# ST_LINK_V2.net
KiCad netlist of a schematic drawn in Altium Designer
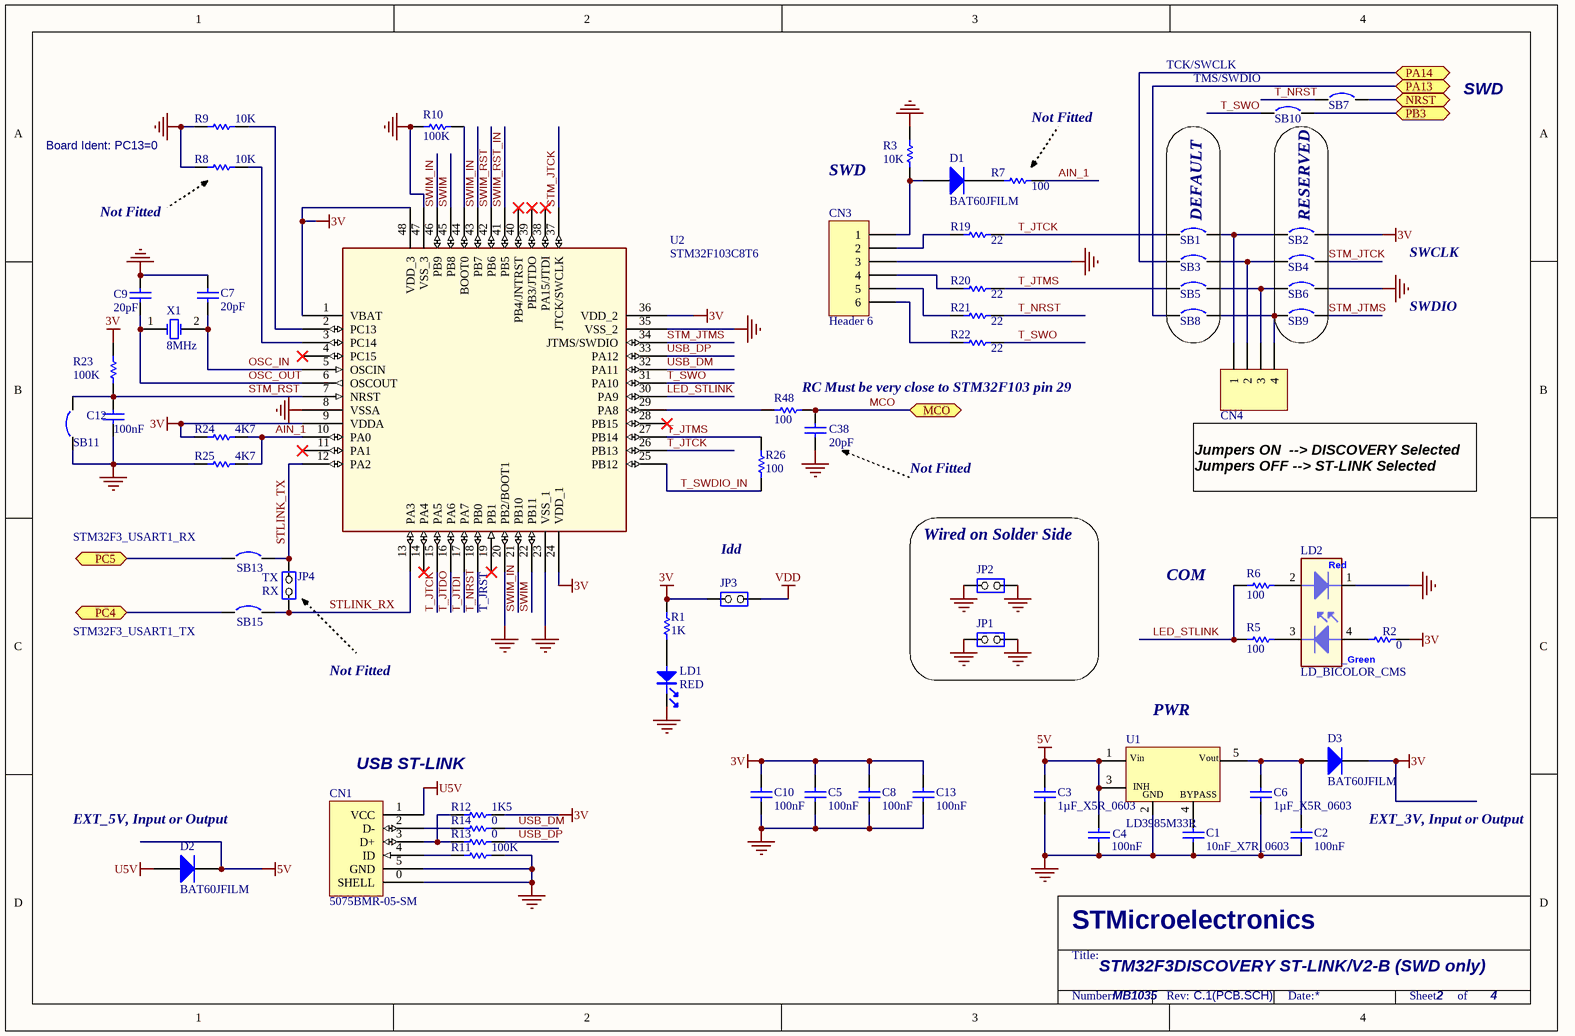
[diagram p0: ST_LINK_V2.SCHDOC]

(export (version "E")
  (design (tool "Eeschema 10.0.6"))
  (components
    (comp (ref "C1")
      (value "10nF_X7R_0603")
      (footprint "0603C")
      (description "0603  X7R 10NF")
      (fields (field (name "TOLERANCE") "10%"))
      (libsource (lib "MB963_1") (part "CAP SMD 0603  X7R 10000PF 50V 10%"))
    )
    (comp (ref "C2")
      (value "100nF")
      (footprint "0603C")
      (description "Capacitor")
      (fields (field (name "PUBLISHER") "Altium Limited"))
      (libsource (lib "MB915_1") (part "Cap"))
    )
    (comp (ref "C3")
      (value "1µF_X5R_0603")
      (footprint "0603C")
      (description "0603  X5R 1µF")
      (fields (field (name "TOLERANCE") "10%"))
      (libsource (lib "MB963_1") (part "CAP SMD 0603  X5R 1µF 25V 10%"))
    )
    (comp (ref "C4")
      (value "100nF")
      (footprint "0603C")
      (description "Capacitor")
      (fields (field (name "PUBLISHER") "Altium Limited"))
      (libsource (lib "MB915_1") (part "Cap"))
    )
    (comp (ref "C5")
      (value "100nF")
      (footprint "0402C")
      (description "Capacitor")
      (fields (field (name "PUBLISHER") "Altium Limited"))
      (libsource (lib "MB915_1") (part "Cap"))
    )
    (comp (ref "C6")
      (value "1µF_X5R_0603")
      (footprint "0603C")
      (description "0603  X5R 1µF")
      (fields (field (name "TOLERANCE") "10%"))
      (libsource (lib "MB963_1") (part "CAP SMD 0603  X5R 1µF 25V 10%"))
    )
    (comp (ref "C7")
      (value "20pF")
      (footprint "0402C")
      (description "Capacitor")
      (fields (field (name "PUBLISHER") "Altium Limited"))
      (libsource (lib "MB915_1") (part "Cap"))
    )
    (comp (ref "C8")
      (value "100nF")
      (footprint "0402C")
      (description "Capacitor")
      (fields (field (name "PUBLISHER") "Altium Limited"))
      (libsource (lib "MB915_1") (part "Cap"))
    )
    (comp (ref "C9")
      (value "20pF")
      (footprint "0402C")
      (description "Capacitor")
      (fields (field (name "PUBLISHER") "Altium Limited"))
      (libsource (lib "MB915_1") (part "Cap"))
    )
    (comp (ref "C10")
      (value "100nF")
      (footprint "0402C")
      (description "Capacitor")
      (fields (field (name "PUBLISHER") "Altium Limited"))
      (libsource (lib "MB915_1") (part "Cap"))
    )
    (comp (ref "C12")
      (value "100nF")
      (footprint "0402C")
      (description "Capacitor")
      (fields (field (name "PUBLISHER") "Altium Limited"))
      (libsource (lib "MB915_1") (part "Cap"))
    )
    (comp (ref "C13")
      (value "100nF")
      (footprint "0402C")
      (description "Capacitor")
      (fields (field (name "PUBLISHER") "Altium Limited"))
      (libsource (lib "MB915_1") (part "Cap"))
    )
    (comp (ref "C38")
      (value "20pF")
      (footprint "0402C")
      (description "Capacitor")
      (fields (field (name "PUBLISHER") "Altium Limited"))
      (libsource (lib "MB915_1") (part "Cap"))
    )
    (comp (ref "CN1")
      (value "5075BMR-05-SM")
      (footprint "USB-MINI-B-SMD")
      (libsource (lib "MCD_TOOLS") (part "USB-MINI-typeB connector"))
    )
    (comp (ref "CN3")
      (value "Header 6")
      (footprint "HDR1X6")
      (description "Header, 6-Pin")
      (fields (field (name "PUBLISHER") "Altium Limited"))
      (libsource (lib "Miscellaneous Connectors") (part "Header 6"))
    )
    (comp (ref "CN4")
      (value "Header 4")
      (footprint "Header 4")
      (description "Header, 4-Pin")
      (fields (field (name "PUBLISHER") "Altium Limited"))
      (libsource (lib "MB963_1") (part "Header 4"))
    )
    (comp (ref "D1")
      (value "BAT60JFILM")
      (footprint "SOD323/A")
      (fields (field (name "PUBLISHER") "Altium Limited"))
      (libsource (lib "MB997") (part "BAT60JFILM"))
    )
    (comp (ref "D2")
      (value "BAT60JFILM")
      (footprint "SOD323/A")
      (fields (field (name "PUBLISHER") "Altium Limited"))
      (libsource (lib "MB997") (part "BAT60JFILM"))
    )
    (comp (ref "D3")
      (value "BAT60JFILM")
      (footprint "SOD323/A")
      (fields (field (name "PUBLISHER") "Altium Limited"))
      (libsource (lib "MB997") (part "BAT60JFILM"))
    )
    (comp (ref "JP1") (value "~") (footprint "SIP2/2.54") (libsource (lib "*") (part "JP2")))
    (comp (ref "JP2") (value "~") (footprint "SIP2/2.54") (libsource (lib "*") (part "JP2")))
    (comp (ref "JP3") (value "~") (footprint "SIP2/2.54") (libsource (lib "*") (part "JP2")))
    (comp (ref "JP4") (value "JP2") (footprint "SIP2/2.54") (libsource (lib "MCD_TOOLS") (part "JP2")))
    (comp (ref "LD1") (value "RED") (footprint "0603D") (libsource (lib "MB963_1") (part "PHOTO")))
    (comp (ref "LD2")
      (value "LD_BICOLOR_CMS")
      (footprint "HSMF-A201")
      (description "Bicolor Led")
      (libsource (lib "MB963") (part "LD_BICOLOR_CMS"))
    )
    (comp (ref "R1")
      (value "1K")
      (footprint "0402R")
      (description "Resistor")
      (fields (field (name "PUBLISHER") "Altium Limited"))
      (libsource (lib "MB915_1") (part "res1"))
    )
    (comp (ref "R2")
      (value "0")
      (footprint "0402R")
      (description "Resistor")
      (fields (field (name "PUBLISHER") "Altium Limited"))
      (libsource (lib "MB915_1") (part "res1"))
    )
    (comp (ref "R3")
      (value "10K")
      (footprint "0402R")
      (description "Resistor")
      (fields (field (name "PUBLISHER") "Altium Limited"))
      (libsource (lib "MB915_1") (part "res1"))
    )
    (comp (ref "R5")
      (value "100")
      (footprint "0402R")
      (description "Resistor")
      (fields (field (name "PUBLISHER") "Altium Limited"))
      (libsource (lib "MB915_1") (part "res1"))
    )
    (comp (ref "R6")
      (value "100")
      (footprint "0402R")
      (description "Resistor")
      (fields (field (name "PUBLISHER") "Altium Limited"))
      (libsource (lib "MB915_1") (part "res1"))
    )
    (comp (ref "R7")
      (value "100")
      (footprint "0402R")
      (description "Resistor")
      (fields (field (name "PUBLISHER") "Altium Limited"))
      (libsource (lib "MB915_1") (part "res1"))
    )
    (comp (ref "R8")
      (value "10K")
      (footprint "0402R")
      (description "Resistor")
      (fields (field (name "PUBLISHER") "Altium Limited"))
      (libsource (lib "MB915_1") (part "res1"))
    )
    (comp (ref "R9")
      (value "10K")
      (footprint "0402R")
      (description "Resistor")
      (fields (field (name "PUBLISHER") "Altium Limited"))
      (libsource (lib "MB915_1") (part "res1"))
    )
    (comp (ref "R10")
      (value "100K")
      (footprint "0402R")
      (description "Resistor")
      (fields (field (name "PUBLISHER") "Altium Limited"))
      (libsource (lib "MB915_1") (part "res1"))
    )
    (comp (ref "R11")
      (value "100K")
      (footprint "0402R")
      (description "Resistor")
      (fields (field (name "PUBLISHER") "Altium Limited"))
      (libsource (lib "MB915_1") (part "res1"))
    )
    (comp (ref "R12")
      (value "1K5")
      (footprint "0402R")
      (description "Resistor")
      (fields (field (name "PUBLISHER") "Altium Limited"))
      (libsource (lib "MB915_1") (part "res1"))
    )
    (comp (ref "R13")
      (value "0")
      (footprint "0402R")
      (description "Resistor")
      (fields (field (name "PUBLISHER") "Altium Limited"))
      (libsource (lib "MB915_1") (part "res1"))
    )
    (comp (ref "R14")
      (value "0")
      (footprint "0402R")
      (description "Resistor")
      (fields (field (name "PUBLISHER") "Altium Limited"))
      (libsource (lib "MB915_1") (part "res1"))
    )
    (comp (ref "R19")
      (value "22")
      (footprint "0402R")
      (description "Resistor")
      (fields (field (name "PUBLISHER") "Altium Limited"))
      (libsource (lib "MB915_1") (part "res1"))
    )
    (comp (ref "R20")
      (value "22")
      (footprint "0402R")
      (description "Resistor")
      (fields (field (name "PUBLISHER") "Altium Limited"))
      (libsource (lib "MB915_1") (part "res1"))
    )
    (comp (ref "R21")
      (value "22")
      (footprint "0402R")
      (description "Resistor")
      (fields (field (name "PUBLISHER") "Altium Limited"))
      (libsource (lib "MB915_1") (part "res1"))
    )
    (comp (ref "R22")
      (value "22")
      (footprint "0402R")
      (description "Resistor")
      (fields (field (name "PUBLISHER") "Altium Limited"))
      (libsource (lib "MB915_1") (part "res1"))
    )
    (comp (ref "R23")
      (value "100K")
      (footprint "0402R")
      (description "Resistor")
      (fields (field (name "PUBLISHER") "Altium Limited"))
      (libsource (lib "MB915_1") (part "res1"))
    )
    (comp (ref "R24")
      (value "4K7")
      (footprint "0402R")
      (description "Resistor")
      (fields (field (name "PUBLISHER") "Altium Limited"))
      (libsource (lib "MB915_1") (part "res1"))
    )
    (comp (ref "R25")
      (value "4K7")
      (footprint "0402R")
      (description "Resistor")
      (fields (field (name "PUBLISHER") "Altium Limited"))
      (libsource (lib "MB915_1") (part "res1"))
    )
    (comp (ref "R26")
      (value "100")
      (footprint "0402R")
      (description "Resistor")
      (fields (field (name "PUBLISHER") "Altium Limited"))
      (libsource (lib "MB915_1") (part "res1"))
    )
    (comp (ref "R48")
      (value "100")
      (footprint "0402R")
      (description "Resistor")
      (fields (field (name "PUBLISHER") "Altium Limited"))
      (libsource (lib "MB915_1") (part "res1"))
    )
    (comp (ref "SB1")
      (value "Circuit Breaker")
      (footprint "JP2_SMD")
      (fields (field (name "PUBLISHER") "Altium Limited"))
      (libsource (lib "MB915") (part "Circuit Breaker"))
    )
    (comp (ref "SB2")
      (value "Circuit Breaker")
      (footprint "JP2_SMD")
      (fields (field (name "PUBLISHER") "Altium Limited"))
      (libsource (lib "MB915") (part "Circuit Breaker"))
    )
    (comp (ref "SB3")
      (value "Circuit Breaker")
      (footprint "JP2_SMD")
      (fields (field (name "PUBLISHER") "Altium Limited"))
      (libsource (lib "MB915") (part "Circuit Breaker"))
    )
    (comp (ref "SB4")
      (value "Circuit Breaker")
      (footprint "JP2_SMD")
      (fields (field (name "PUBLISHER") "Altium Limited"))
      (libsource (lib "MB915") (part "Circuit Breaker"))
    )
    (comp (ref "SB5")
      (value "Circuit Breaker")
      (footprint "JP2_SMD")
      (fields (field (name "PUBLISHER") "Altium Limited"))
      (libsource (lib "MB915") (part "Circuit Breaker"))
    )
    (comp (ref "SB6")
      (value "Circuit Breaker")
      (footprint "JP2_SMD")
      (fields (field (name "PUBLISHER") "Altium Limited"))
      (libsource (lib "MB915") (part "Circuit Breaker"))
    )
    (comp (ref "SB7")
      (value "Circuit Breaker")
      (footprint "JP2_SMD")
      (fields (field (name "PUBLISHER") "Altium Limited"))
      (libsource (lib "MB915") (part "Circuit Breaker"))
    )
    (comp (ref "SB8")
      (value "Circuit Breaker")
      (footprint "JP2_SMD")
      (fields (field (name "PUBLISHER") "Altium Limited"))
      (libsource (lib "MB915") (part "Circuit Breaker"))
    )
    (comp (ref "SB9")
      (value "Circuit Breaker")
      (footprint "JP2_SMD")
      (fields (field (name "PUBLISHER") "Altium Limited"))
      (libsource (lib "MB915") (part "Circuit Breaker"))
    )
    (comp (ref "SB10")
      (value "Circuit Breaker")
      (footprint "JP2_SMD")
      (fields (field (name "PUBLISHER") "Altium Limited"))
      (libsource (lib "MCD_TOOLS") (part "Circuit Breaker"))
    )
    (comp (ref "SB11")
      (value "Circuit Breaker")
      (footprint "JP2_SMD")
      (fields (field (name "PUBLISHER") "Altium Limited"))
      (libsource (lib "MB915") (part "Circuit Breaker"))
    )
    (comp (ref "SB13")
      (value "Circuit Breaker")
      (footprint "JP2_SMD")
      (fields (field (name "PUBLISHER") "Altium Limited"))
      (libsource (lib "MCD_TOOLS") (part "Circuit Breaker"))
    )
    (comp (ref "SB15")
      (value "Circuit Breaker")
      (footprint "JP2_SMD")
      (fields (field (name "PUBLISHER") "Altium Limited"))
      (libsource (lib "MCD_TOOLS") (part "Circuit Breaker"))
    )
    (comp (ref "U1")
      (value "LD3985M33R")
      (footprint "SOT-23-5L")
      (description "Ultra low drop-low noise BiCMOS voltage, regulators low ESR capacitors compatible")
      (libsource (lib "MCD_TOOLS") (part "LD3985M33R"))
    )
    (comp (ref "U2")
      (value "STM32F103C8T6")
      (footprint "QFP48 7X7")
      (description "Medium-density performance line ARM-based 32-bit MCU with 64KB Flash")
      (libsource (lib "MCD_TOOLS") (part "STM32F103C8T6"))
    )
    (comp (ref "X1")
      (value "8MHz")
      (footprint "XTAL1")
      (description "Crystal Oscillator")
      (fields (field (name "PUBLISHER") "Altium Limited"))
      (libsource (lib "MB963_1") (part "XTAL"))
    )
  )
  (nets
    (net (code "1") (name "/AIN_1") (class "Default")
      (node (ref "R24") (pin "2") (pinfunction "2_2") (pintype "passive"))
      (node (ref "R25") (pin "2") (pinfunction "2_2") (pintype "passive"))
      (node (ref "R7") (pin "2") (pinfunction "2_2") (pintype "passive"))
      (node (ref "U2") (pin "10") (pinfunction "PA0_10") (pintype "bidirectional"))
    )
    (net (code "2") (name "/LED_STLINK") (class "Default")
      (node (ref "R5") (pin "1") (pinfunction "1_1") (pintype "passive"))
      (node (ref "R6") (pin "1") (pinfunction "1_1") (pintype "passive"))
      (node (ref "U2") (pin "30") (pinfunction "PA9_30") (pintype "bidirectional"))
    )
    (net (code "3") (name "/MCO") (class "Default")
      (node (ref "C38") (pin "1") (pinfunction "1_1") (pintype "passive"))
      (node (ref "R48") (pin "2") (pinfunction "2_2") (pintype "passive"))
    )
    (net (code "4") (name "/NRST") (class "Default")
      (node (ref "SB7") (pin "2") (pinfunction "2_2") (pintype "passive"))
    )
    (net (code "5") (name "/OSC_IN") (class "Default")
      (node (ref "C7") (pin "2") (pinfunction "2_2") (pintype "passive"))
      (node (ref "U2") (pin "5") (pinfunction "OSCIN_5") (pintype "input"))
      (node (ref "X1") (pin "2") (pinfunction "OSC2_2") (pintype "passive"))
    )
    (net (code "6") (name "/OSC_OUT") (class "Default")
      (node (ref "C9") (pin "2") (pinfunction "2_2") (pintype "passive"))
      (node (ref "U2") (pin "6") (pinfunction "OSCOUT_6") (pintype "output"))
      (node (ref "X1") (pin "1") (pinfunction "OSC1_1") (pintype "passive"))
    )
    (net (code "7") (name "/PA13") (class "Default")
      (node (ref "SB8") (pin "1") (pinfunction "1_1") (pintype "passive"))
    )
    (net (code "8") (name "/PA14") (class "Default")
      (node (ref "SB3") (pin "1") (pinfunction "1_1") (pintype "passive"))
    )
    (net (code "9") (name "/PB3") (class "Default")
      (node (ref "SB10") (pin "2") (pinfunction "2_2") (pintype "passive"))
    )
    (net (code "10") (name "/PC4") (class "Default")
      (node (ref "SB15") (pin "1") (pinfunction "1_1") (pintype "passive"))
    )
    (net (code "11") (name "/PC5") (class "Default")
      (node (ref "SB13") (pin "1") (pinfunction "1_1") (pintype "passive"))
    )
    (net (code "12") (name "/STLINK_RX") (class "Default")
      (node (ref "JP4") (pin "1") (pinfunction "COMMON_1") (pintype "passive"))
      (node (ref "SB15") (pin "2") (pinfunction "2_2") (pintype "passive"))
      (node (ref "U2") (pin "13") (pinfunction "PA3_13") (pintype "bidirectional"))
    )
    (net (code "13") (name "/STLINK_TX") (class "Default")
      (node (ref "JP4") (pin "2") (pinfunction "NO_2") (pintype "passive"))
      (node (ref "SB13") (pin "2") (pinfunction "2_2") (pintype "passive"))
      (node (ref "U2") (pin "12") (pinfunction "PA2_12") (pintype "bidirectional"))
    )
    (net (code "14") (name "/STM_JTCK") (class "Default")
      (node (ref "SB4") (pin "2") (pinfunction "2_2") (pintype "passive"))
      (node (ref "U2") (pin "37") (pinfunction "JTCK/SWCLK_37") (pintype "bidirectional"))
    )
    (net (code "15") (name "/STM_JTMS") (class "Default")
      (node (ref "SB9") (pin "2") (pinfunction "2_2") (pintype "passive"))
      (node (ref "U2") (pin "34") (pinfunction "JTMS/SWDIO_34") (pintype "bidirectional"))
    )
    (net (code "16") (name "/STM_RST") (class "Default")
      (node (ref "C12") (pin "2") (pinfunction "2_2") (pintype "passive"))
      (node (ref "R23") (pin "1") (pinfunction "1_1") (pintype "passive"))
      (node (ref "SB11") (pin "2") (pinfunction "2_2") (pintype "passive"))
      (node (ref "U2") (pin "7") (pinfunction "NRST_7") (pintype "input"))
    )
    (net (code "17") (name "/SWIM") (class "Default")
      (node (ref "U2") (pin "22") (pinfunction "PB11_22") (pintype "bidirectional"))
      (node (ref "U2") (pin "45") (pinfunction "PB8_45") (pintype "bidirectional"))
    )
    (net (code "18") (name "/SWIM_IN") (class "Default")
      (node (ref "U2") (pin "21") (pinfunction "PB10_21") (pintype "bidirectional"))
      (node (ref "U2") (pin "43") (pinfunction "PB7_43") (pintype "bidirectional"))
      (node (ref "U2") (pin "46") (pinfunction "PB9_46") (pintype "bidirectional"))
    )
    (net (code "19") (name "/SWIM_RST") (class "Default")
      (node (ref "U2") (pin "42") (pinfunction "PB6_42") (pintype "bidirectional"))
    )
    (net (code "20") (name "/SWIM_RST_IN") (class "Default")
      (node (ref "U2") (pin "41") (pinfunction "PB5_41") (pintype "bidirectional"))
    )
    (net (code "21") (name "/T_JTCK") (class "Default")
      (node (ref "R19") (pin "2") (pinfunction "2_2") (pintype "passive"))
      (node (ref "SB1") (pin "1") (pinfunction "1_1") (pintype "passive"))
      (node (ref "U2") (pin "15") (pinfunction "PA5_15") (pintype "bidirectional"))
      (node (ref "U2") (pin "26") (pinfunction "PB13_26") (pintype "bidirectional"))
    )
    (net (code "22") (name "/T_JTDI") (class "Default")
      (node (ref "U2") (pin "17") (pinfunction "PA7_17") (pintype "bidirectional"))
    )
    (net (code "23") (name "/T_JTDO") (class "Default")
      (node (ref "U2") (pin "16") (pinfunction "PA6_16") (pintype "bidirectional"))
    )
    (net (code "24") (name "/T_JTMS") (class "Default")
      (node (ref "R20") (pin "2") (pinfunction "2_2") (pintype "passive"))
      (node (ref "R26") (pin "2") (pinfunction "2_2") (pintype "passive"))
      (node (ref "SB5") (pin "1") (pinfunction "1_1") (pintype "passive"))
      (node (ref "U2") (pin "27") (pinfunction "PB14_27") (pintype "bidirectional"))
    )
    (net (code "25") (name "/T_NRST") (class "Default")
      (node (ref "R21") (pin "2") (pinfunction "2_2") (pintype "passive"))
      (node (ref "SB7") (pin "1") (pinfunction "1_1") (pintype "passive"))
      (node (ref "U2") (pin "18") (pinfunction "PB0_18") (pintype "bidirectional"))
    )
    (net (code "26") (name "/T_SWDIO_IN") (class "Default")
      (node (ref "R26") (pin "1") (pinfunction "1_1") (pintype "passive"))
      (node (ref "U2") (pin "25") (pinfunction "PB12_25") (pintype "bidirectional"))
    )
    (net (code "27") (name "/T_SWO") (class "Default")
      (node (ref "R22") (pin "2") (pinfunction "2_2") (pintype "passive"))
      (node (ref "SB10") (pin "1") (pinfunction "1_1") (pintype "passive"))
      (node (ref "U2") (pin "31") (pinfunction "PA10_31") (pintype "bidirectional"))
    )
    (net (code "28") (name "/USB_DM") (class "Default")
      (node (ref "R14") (pin "2") (pinfunction "2_2") (pintype "passive"))
      (node (ref "U2") (pin "32") (pinfunction "PA11_32") (pintype "bidirectional"))
    )
    (net (code "29") (name "/USB_DP") (class "Default")
      (node (ref "R13") (pin "2") (pinfunction "2_2") (pintype "passive"))
      (node (ref "U2") (pin "33") (pinfunction "PA12_33") (pintype "bidirectional"))
    )
    (net (code "30") (name "3V") (class "Default")
      (node (ref "C10") (pin "2") (pinfunction "2_2") (pintype "passive"))
      (node (ref "C13") (pin "2") (pinfunction "2_2") (pintype "passive"))
      (node (ref "C5") (pin "2") (pinfunction "2_2") (pintype "passive"))
      (node (ref "C8") (pin "1") (pinfunction "1_1") (pintype "passive"))
      (node (ref "D3") (pin "2") (pinfunction "K_2") (pintype "passive"))
      (node (ref "JP3") (pin "1") (pinfunction "COMMON_1") (pintype "passive"))
      (node (ref "R1") (pin "2") (pinfunction "2_2") (pintype "passive"))
      (node (ref "R12") (pin "2") (pinfunction "2_2") (pintype "passive"))
      (node (ref "R2") (pin "2") (pinfunction "2_2") (pintype "passive"))
      (node (ref "R23") (pin "2") (pinfunction "2_2") (pintype "passive"))
      (node (ref "R24") (pin "1") (pinfunction "1_1") (pintype "passive"))
      (node (ref "SB2") (pin "2") (pinfunction "2_2") (pintype "passive"))
      (node (ref "U2") (pin "1") (pinfunction "VBAT_1") (pintype "power_in"))
      (node (ref "U2") (pin "24") (pinfunction "VDD_1_24") (pintype "power_in"))
      (node (ref "U2") (pin "36") (pinfunction "VDD_2_36") (pintype "power_in"))
      (node (ref "U2") (pin "48") (pinfunction "VDD_3_48") (pintype "power_in"))
      (node (ref "U2") (pin "9") (pinfunction "VDDA_9") (pintype "power_in"))
    )
    (net (code "31") (name "5V") (class "Default")
      (node (ref "C3") (pin "2") (pinfunction "2_2") (pintype "passive"))
      (node (ref "C4") (pin "2") (pinfunction "2_2") (pintype "passive"))
      (node (ref "D2") (pin "2") (pinfunction "K_2") (pintype "passive"))
      (node (ref "U1") (pin "1") (pinfunction "Vin_1") (pintype "passive"))
      (node (ref "U1") (pin "3") (pinfunction "CE_3") (pintype "passive"))
    )
    (net (code "32") (name "GND") (class "Default")
      (node (ref "C1") (pin "1") (pinfunction "1_1") (pintype "passive"))
      (node (ref "C10") (pin "1") (pinfunction "1_1") (pintype "passive"))
      (node (ref "C12") (pin "1") (pinfunction "1_1") (pintype "passive"))
      (node (ref "C13") (pin "1") (pinfunction "1_1") (pintype "passive"))
      (node (ref "C2") (pin "1") (pinfunction "1_1") (pintype "passive"))
      (node (ref "C3") (pin "1") (pinfunction "1_1") (pintype "passive"))
      (node (ref "C38") (pin "2") (pinfunction "2_2") (pintype "passive"))
      (node (ref "C4") (pin "1") (pinfunction "1_1") (pintype "passive"))
      (node (ref "C5") (pin "1") (pinfunction "1_1") (pintype "passive"))
      (node (ref "C6") (pin "2") (pinfunction "2_2") (pintype "passive"))
      (node (ref "C7") (pin "1") (pinfunction "1_1") (pintype "passive"))
      (node (ref "C8") (pin "2") (pinfunction "2_2") (pintype "passive"))
      (node (ref "C9") (pin "1") (pinfunction "1_1") (pintype "passive"))
      (node (ref "CN1") (pin "0") (pinfunction "SHELL_0") (pintype "power_in"))
      (node (ref "CN1") (pin "5") (pinfunction "GND_5") (pintype "power_in"))
      (node (ref "CN3") (pin "3") (pinfunction "3_3") (pintype "passive"))
      (node (ref "JP1") (pin "1") (pinfunction "COMMON_1") (pintype "passive"))
      (node (ref "JP1") (pin "2") (pinfunction "NO_2") (pintype "passive"))
      (node (ref "JP2") (pin "1") (pinfunction "COMMON_1") (pintype "passive"))
      (node (ref "JP2") (pin "2") (pinfunction "NO_2") (pintype "passive"))
      (node (ref "LD1") (pin "2") (pintype "passive"))
      (node (ref "LD2") (pin "1") (pinfunction "1_1") (pintype "passive"))
      (node (ref "R10") (pin "1") (pinfunction "1_1") (pintype "passive"))
      (node (ref "R11") (pin "2") (pinfunction "2_2") (pintype "passive"))
      (node (ref "R25") (pin "1") (pinfunction "1_1") (pintype "passive"))
      (node (ref "R3") (pin "2") (pinfunction "2_2") (pintype "passive"))
      (node (ref "R8") (pin "1") (pinfunction "1_1") (pintype "passive"))
      (node (ref "R9") (pin "1") (pinfunction "1_1") (pintype "passive"))
      (node (ref "SB11") (pin "1") (pinfunction "1_1") (pintype "passive"))
      (node (ref "SB6") (pin "2") (pinfunction "2_2") (pintype "passive"))
      (node (ref "U1") (pin "2") (pinfunction "GND_2") (pintype "passive"))
      (node (ref "U2") (pin "20") (pinfunction "PB2/BOOT1_20") (pintype "bidirectional"))
      (node (ref "U2") (pin "23") (pinfunction "VSS_1_23") (pintype "power_in"))
      (node (ref "U2") (pin "35") (pinfunction "VSS_2_35") (pintype "power_in"))
      (node (ref "U2") (pin "47") (pinfunction "VSS_3_47") (pintype "power_in"))
      (node (ref "U2") (pin "8") (pinfunction "VSSA_8") (pintype "power_in"))
    )
    (net (code "33") (name "Net-(CN1-D+)") (class "Default")
      (node (ref "CN1") (pin "3") (pinfunction "D+_3") (pintype "bidirectional"))
      (node (ref "R12") (pin "1") (pinfunction "1_1") (pintype "passive"))
      (node (ref "R13") (pin "1") (pinfunction "1_1") (pintype "passive"))
    )
    (net (code "34") (name "Net-(CN1-D-)") (class "Default")
      (node (ref "CN1") (pin "2") (pinfunction "D-_2") (pintype "bidirectional"))
      (node (ref "R14") (pin "1") (pinfunction "1_1") (pintype "passive"))
    )
    (net (code "35") (name "Net-(CN1-ID)") (class "Default")
      (node (ref "CN1") (pin "4") (pinfunction "ID_4") (pintype "input"))
      (node (ref "R11") (pin "1") (pinfunction "1_1") (pintype "passive"))
    )
    (net (code "36") (name "Net-(CN3-Pad2)") (class "Default")
      (node (ref "CN3") (pin "2") (pinfunction "2_2") (pintype "passive"))
      (node (ref "R19") (pin "1") (pinfunction "1_1") (pintype "passive"))
    )
    (net (code "37") (name "Net-(CN3-Pad4)") (class "Default")
      (node (ref "CN3") (pin "4") (pinfunction "4_4") (pintype "passive"))
      (node (ref "R20") (pin "1") (pinfunction "1_1") (pintype "passive"))
    )
    (net (code "38") (name "Net-(CN3-Pad5)") (class "Default")
      (node (ref "CN3") (pin "5") (pinfunction "5_5") (pintype "passive"))
      (node (ref "R21") (pin "1") (pinfunction "1_1") (pintype "passive"))
    )
    (net (code "39") (name "Net-(CN3-Pad6)") (class "Default")
      (node (ref "CN3") (pin "6") (pinfunction "6_6") (pintype "passive"))
      (node (ref "R22") (pin "1") (pinfunction "1_1") (pintype "passive"))
    )
    (net (code "40") (name "Net-(CN4-Pad1)") (class "Default")
      (node (ref "CN4") (pin "1") (pinfunction "1_1") (pintype "passive"))
      (node (ref "SB1") (pin "2") (pinfunction "2_2") (pintype "passive"))
      (node (ref "SB2") (pin "1") (pinfunction "1_1") (pintype "passive"))
    )
    (net (code "41") (name "Net-(CN4-Pad2)") (class "Default")
      (node (ref "CN4") (pin "2") (pinfunction "2_2") (pintype "passive"))
      (node (ref "SB3") (pin "2") (pinfunction "2_2") (pintype "passive"))
      (node (ref "SB4") (pin "1") (pinfunction "1_1") (pintype "passive"))
    )
    (net (code "42") (name "Net-(CN4-Pad3)") (class "Default")
      (node (ref "CN4") (pin "3") (pinfunction "3_3") (pintype "passive"))
      (node (ref "SB5") (pin "2") (pinfunction "2_2") (pintype "passive"))
      (node (ref "SB6") (pin "1") (pinfunction "1_1") (pintype "passive"))
    )
    (net (code "43") (name "Net-(CN4-Pad4)") (class "Default")
      (node (ref "CN4") (pin "4") (pinfunction "4_4") (pintype "passive"))
      (node (ref "SB8") (pin "2") (pinfunction "2_2") (pintype "passive"))
      (node (ref "SB9") (pin "1") (pinfunction "1_1") (pintype "passive"))
    )
    (net (code "44") (name "Net-(D1-A)") (class "Default")
      (node (ref "CN3") (pin "1") (pinfunction "1_1") (pintype "passive"))
      (node (ref "D1") (pin "1") (pinfunction "A_1") (pintype "passive"))
      (node (ref "R3") (pin "1") (pinfunction "1_1") (pintype "passive"))
    )
    (net (code "45") (name "Net-(D1-K)") (class "Default")
      (node (ref "D1") (pin "2") (pinfunction "K_2") (pintype "passive"))
      (node (ref "R7") (pin "1") (pinfunction "1_1") (pintype "passive"))
    )
    (net (code "46") (name "Net-(D3-A)") (class "Default")
      (node (ref "C2") (pin "2") (pinfunction "2_2") (pintype "passive"))
      (node (ref "C6") (pin "1") (pinfunction "1_1") (pintype "passive"))
      (node (ref "D3") (pin "1") (pinfunction "A_1") (pintype "passive"))
      (node (ref "U1") (pin "5") (pinfunction "Vout_5") (pintype "passive"))
    )
    (net (code "47") (name "Net-(LD1-Pad1)") (class "Default")
      (node (ref "LD1") (pin "1") (pintype "passive"))
      (node (ref "R1") (pin "1") (pinfunction "1_1") (pintype "passive"))
    )
    (net (code "48") (name "Net-(LD2-Pad2)") (class "Default")
      (node (ref "LD2") (pin "2") (pinfunction "2_2") (pintype "passive"))
      (node (ref "R6") (pin "2") (pinfunction "2_2") (pintype "passive"))
    )
    (net (code "49") (name "Net-(LD2-Pad3)") (class "Default")
      (node (ref "LD2") (pin "3") (pinfunction "3_3") (pintype "passive"))
      (node (ref "R5") (pin "2") (pinfunction "2_2") (pintype "passive"))
    )
    (net (code "50") (name "Net-(LD2-Pad4)") (class "Default")
      (node (ref "LD2") (pin "4") (pinfunction "4_4") (pintype "passive"))
      (node (ref "R2") (pin "1") (pinfunction "1_1") (pintype "passive"))
    )
    (net (code "51") (name "Net-(U1-BYPASS)") (class "Default")
      (node (ref "C1") (pin "2") (pinfunction "2_2") (pintype "passive"))
      (node (ref "U1") (pin "4") (pinfunction "BYPASS_4") (pintype "passive"))
    )
    (net (code "52") (name "Net-(U2-BOOT0)") (class "Default")
      (node (ref "R10") (pin "2") (pinfunction "2_2") (pintype "passive"))
      (node (ref "U2") (pin "44") (pinfunction "BOOT0_44") (pintype "bidirectional"))
    )
    (net (code "53") (name "Net-(U2-PA8)") (class "Default")
      (node (ref "R48") (pin "1") (pinfunction "1_1") (pintype "passive"))
      (node (ref "U2") (pin "29") (pinfunction "PA8_29") (pintype "bidirectional"))
    )
    (net (code "54") (name "Net-(U2-PC13)") (class "Default")
      (node (ref "R9") (pin "2") (pinfunction "2_2") (pintype "passive"))
      (node (ref "U2") (pin "2") (pinfunction "PC13_2") (pintype "bidirectional"))
    )
    (net (code "55") (name "Net-(U2-PC14)") (class "Default")
      (node (ref "R8") (pin "2") (pinfunction "2_2") (pintype "passive"))
      (node (ref "U2") (pin "3") (pinfunction "PC14_3") (pintype "bidirectional"))
    )
    (net (code "56") (name "U5V") (class "Default")
      (node (ref "CN1") (pin "1") (pinfunction "VCC_1") (pintype "power_in"))
      (node (ref "D2") (pin "1") (pinfunction "A_1") (pintype "passive"))
    )
    (net (code "57") (name "VDD") (class "Default")
      (node (ref "JP3") (pin "2") (pinfunction "NO_2") (pintype "passive"))
    )
    (net (code "58") (name "unconnected-(U2-PA1-Pad11)") (class "Default")
      (node (ref "U2") (pin "11") (pinfunction "PA1_11") (pintype "bidirectional+no_connect"))
    )
    (net (code "59") (name "unconnected-(U2-PA4-Pad14)") (class "Default")
      (node (ref "U2") (pin "14") (pinfunction "PA4_14") (pintype "bidirectional+no_connect"))
    )
    (net (code "60") (name "unconnected-(U2-PA15{slash}JTDI-Pad38)") (class "Default")
      (node (ref "U2") (pin "38") (pinfunction "PA15/JTDI_38") (pintype "bidirectional+no_connect"))
    )
    (net (code "61") (name "unconnected-(U2-PB1-Pad19)") (class "Default")
      (node (ref "U2") (pin "19") (pinfunction "PB1_19") (pintype "input+no_connect"))
    )
    (net (code "62") (name "unconnected-(U2-PB3{slash}JTDO-Pad39)") (class "Default")
      (node (ref "U2") (pin "39") (pinfunction "PB3/JTDO_39") (pintype "bidirectional+no_connect"))
    )
    (net (code "63") (name "unconnected-(U2-PB4{slash}JNTRST-Pad40)") (class "Default")
      (node (ref "U2") (pin "40") (pinfunction "PB4/JNTRST_40") (pintype "bidirectional+no_connect"))
    )
    (net (code "64") (name "unconnected-(U2-PB15-Pad28)") (class "Default")
      (node (ref "U2") (pin "28") (pinfunction "PB15_28") (pintype "bidirectional+no_connect"))
    )
    (net (code "65") (name "unconnected-(U2-PC15-Pad4)") (class "Default")
      (node (ref "U2") (pin "4") (pinfunction "PC15_4") (pintype "bidirectional+no_connect"))
    )
  )
)
